# LoRa.net
KiCad netlist of a schematic drawn in Altium Designer
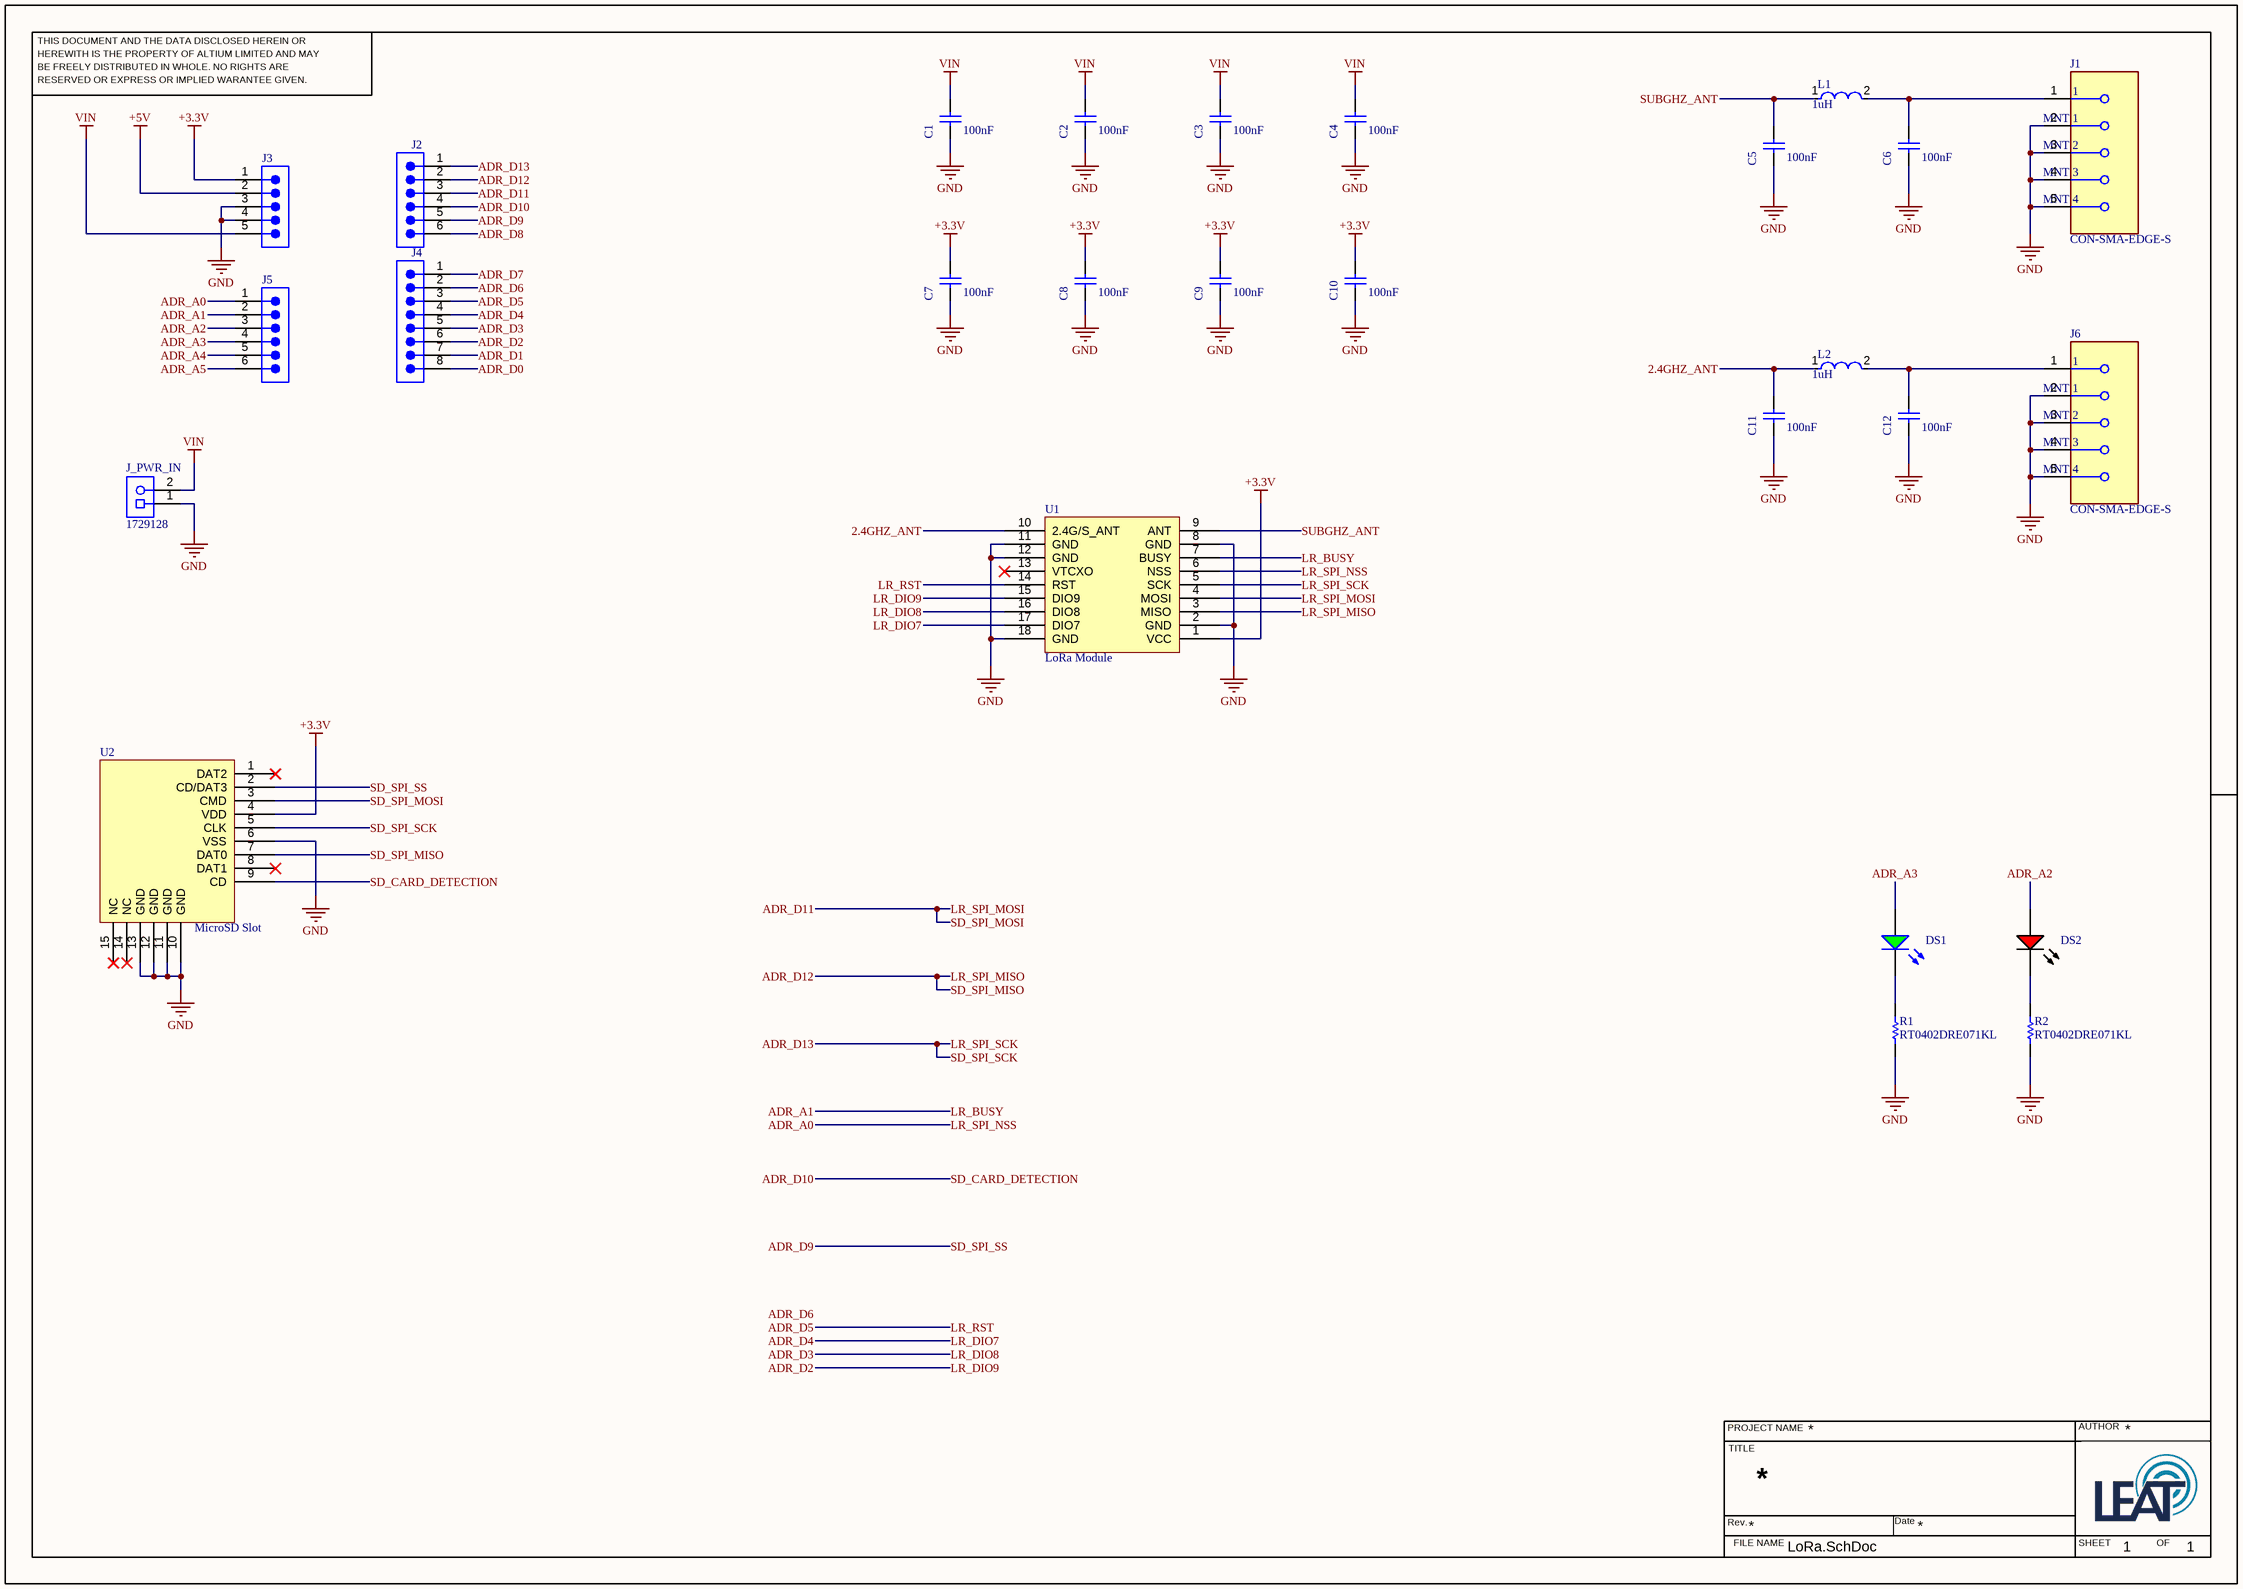
[diagram p0: LoRa.SchDoc]

(export (version "E")
  (design (tool "Eeschema 10.0.6"))
  (components
    (comp (ref "C1")
      (value "885012205037")
      (footprint "WCAP-CSGP_0402_L1W0.5H0.5")
      (description "Cap Ceramic 0.1uF 16V X7R 10% Pad SMD 0402 125C T/R")
      (fields (field (name "CAPACITANCE") "100nF") (field (name "TOLERANCE") "10%"))
      (libsource (lib "Altium Content Vault") (part "Capacitor_Non-Polarized"))
    )
    (comp (ref "C2")
      (value "885012205037")
      (footprint "WCAP-CSGP_0402_L1W0.5H0.5")
      (description "Cap Ceramic 0.1uF 16V X7R 10% Pad SMD 0402 125C T/R")
      (fields (field (name "CAPACITANCE") "100nF") (field (name "TOLERANCE") "10%"))
      (libsource (lib "Altium Content Vault") (part "Capacitor_Non-Polarized"))
    )
    (comp (ref "C3")
      (value "885012205037")
      (footprint "WCAP-CSGP_0402_L1W0.5H0.5")
      (description "Cap Ceramic 0.1uF 16V X7R 10% Pad SMD 0402 125C T/R")
      (fields (field (name "CAPACITANCE") "100nF") (field (name "TOLERANCE") "10%"))
      (libsource (lib "Altium Content Vault") (part "Capacitor_Non-Polarized"))
    )
    (comp (ref "C4")
      (value "885012205037")
      (footprint "WCAP-CSGP_0402_L1W0.5H0.5")
      (description "Cap Ceramic 0.1uF 16V X7R 10% Pad SMD 0402 125C T/R")
      (fields (field (name "CAPACITANCE") "100nF") (field (name "TOLERANCE") "10%"))
      (libsource (lib "Altium Content Vault") (part "Capacitor_Non-Polarized"))
    )
    (comp (ref "C5")
      (value "885012205037")
      (footprint "WCAP-CSGP_0402_L1W0.5H0.5")
      (description "Cap Ceramic 0.1uF 16V X7R 10% Pad SMD 0402 125C T/R")
      (fields (field (name "CAPACITANCE") "100nF") (field (name "TOLERANCE") "10%"))
      (libsource (lib "Altium Content Vault") (part "Capacitor_Non-Polarized"))
    )
    (comp (ref "C6")
      (value "885012205037")
      (footprint "WCAP-CSGP_0402_L1W0.5H0.5")
      (description "Cap Ceramic 0.1uF 16V X7R 10% Pad SMD 0402 125C T/R")
      (fields (field (name "CAPACITANCE") "100nF") (field (name "TOLERANCE") "10%"))
      (libsource (lib "Altium Content Vault") (part "Capacitor_Non-Polarized"))
    )
    (comp (ref "C7")
      (value "885012205037")
      (footprint "WCAP-CSGP_0402_L1W0.5H0.5")
      (description "Cap Ceramic 0.1uF 16V X7R 10% Pad SMD 0402 125C T/R")
      (fields (field (name "CAPACITANCE") "100nF") (field (name "TOLERANCE") "10%"))
      (libsource (lib "Altium Content Vault") (part "Capacitor_Non-Polarized"))
    )
    (comp (ref "C8")
      (value "885012205037")
      (footprint "WCAP-CSGP_0402_L1W0.5H0.5")
      (description "Cap Ceramic 0.1uF 16V X7R 10% Pad SMD 0402 125C T/R")
      (fields (field (name "CAPACITANCE") "100nF") (field (name "TOLERANCE") "10%"))
      (libsource (lib "Altium Content Vault") (part "Capacitor_Non-Polarized"))
    )
    (comp (ref "C9")
      (value "885012205037")
      (footprint "WCAP-CSGP_0402_L1W0.5H0.5")
      (description "Cap Ceramic 0.1uF 16V X7R 10% Pad SMD 0402 125C T/R")
      (fields (field (name "CAPACITANCE") "100nF") (field (name "TOLERANCE") "10%"))
      (libsource (lib "Altium Content Vault") (part "Capacitor_Non-Polarized"))
    )
    (comp (ref "C10")
      (value "885012205037")
      (footprint "WCAP-CSGP_0402_L1W0.5H0.5")
      (description "Cap Ceramic 0.1uF 16V X7R 10% Pad SMD 0402 125C T/R")
      (fields (field (name "CAPACITANCE") "100nF") (field (name "TOLERANCE") "10%"))
      (libsource (lib "Altium Content Vault") (part "Capacitor_Non-Polarized"))
    )
    (comp (ref "C11")
      (value "885012205037")
      (footprint "WCAP-CSGP_0402_L1W0.5H0.5")
      (description "Cap Ceramic 0.1uF 16V X7R 10% Pad SMD 0402 125C T/R")
      (fields (field (name "CAPACITANCE") "100nF") (field (name "TOLERANCE") "10%"))
      (libsource (lib "Altium Content Vault") (part "Capacitor_Non-Polarized"))
    )
    (comp (ref "C12")
      (value "885012205037")
      (footprint "WCAP-CSGP_0402_L1W0.5H0.5")
      (description "Cap Ceramic 0.1uF 16V X7R 10% Pad SMD 0402 125C T/R")
      (fields (field (name "CAPACITANCE") "100nF") (field (name "TOLERANCE") "10%"))
      (libsource (lib "Altium Content Vault") (part "Capacitor_Non-Polarized"))
    )
    (comp (ref "DS1")
      (value "LTST-S220GKT")
      (footprint "LTST-S220GKT_V")
      (description "LED Green, 100 mW, 30 mA, -55 to 85 degC, 2-Pin SMD, RoHS, Tape and Reel")
      (fields (field (name "MANUFACTURER") "Lite-On"))
      (libsource (lib "Altium Content Vault") (part "LED-GREEN-AK-2"))
    )
    (comp (ref "DS2")
      (value "LTST-C170KRKT")
      (footprint "LTST-C170KRKT_V")
      (description "LED Red, 75 mW, 54 mcd, -55 to 85 degC, 2-Pin SMD, RoHS, Tape and Reel")
      (fields (field (name "MANUFACTURER") "Lite-On"))
      (libsource (lib "Altium Content Vault") (part "LED-RED-AK-2"))
    )
    (comp (ref "J1")
      (value "CON-SMA-EDGE-S")
      (footprint "FP-CON-SMA-EDGE-S-MFG")
      (description "CONN SMA JACK STR EDGE MNT")
      (fields
        (field (name "OCTOPART") "https://octopart.com/con-sma-edge-s-rf+solutions-70967450")
        (field (name "MANUFACTURER") "RF Solutions Ltd.")
      )
      (libsource (lib "Altium Content Vault") (part "a163d97a771fcdd2fd1f1a9264c171f"))
    )
    (comp (ref "J2")
      (value "61300611121")
      (footprint "61300611121")
      (description "THT Vertical Pin Header WR-PHD, Pitch 2.54 mm, Single Row, 6 pins")
      (libsource (lib "Altium Content Vault") (part "Header_Male_1R_06P"))
    )
    (comp (ref "J3")
      (value "61300511121")
      (footprint "61300511121")
      (description "THT Vertical Pin Header WR-PHD, Pitch 2.54 mm, Single Row, 5 pins")
      (libsource (lib "Altium Content Vault") (part "Header_Male_1R_05P"))
    )
    (comp (ref "J4")
      (value "61300811121")
      (footprint "61300811121")
      (description "THT Vertical Pin Header WR-PHD, Pitch 2.54 mm, Single Row, 8 pins")
      (libsource (lib "Altium Content Vault") (part "Header_Male_1R_08P"))
    )
    (comp (ref "J5")
      (value "61300611121")
      (footprint "61300611121")
      (description "THT Vertical Pin Header WR-PHD, Pitch 2.54 mm, Single Row, 6 pins")
      (libsource (lib "Altium Content Vault") (part "Header_Male_1R_06P"))
    )
    (comp (ref "J6")
      (value "CON-SMA-EDGE-S")
      (footprint "FP-CON-SMA-EDGE-S-MFG")
      (description "CONN SMA JACK STR EDGE MNT")
      (fields
        (field (name "OCTOPART") "https://octopart.com/con-sma-edge-s-rf+solutions-70967450")
        (field (name "MANUFACTURER") "RF Solutions Ltd.")
      )
      (libsource (lib "Altium Content Vault") (part "a163d97a771fcdd2fd1f1a9264c171f"))
    )
    (comp (ref "J_PWR_IN")
      (value "1729128")
      (footprint "PHOE-1729128-2_V")
      (description "PCB Terminal Block, 13.5 A, 400 V, 2-Pin THD, RoHS, Bulk")
      (fields (field (name "MANUFACTURER") "Phoenix Contact"))
      (libsource (lib "Altium Content Vault") (part "CN-2P-F-R2"))
    )
    (comp (ref "L1")
      (value "MLZ1005M1R0WT000")
      (footprint "FP-MLZ1005-MFG")
      (description "Shielded Multilayer Inductor 1uH ±20% 450mA 455mΩ SMD 0402")
      (fields (field (name "TOLERANCE") "20%") (field (name "INDUCTANCE") "1uH"))
      (libsource (lib "Altium Content Vault") (part "725321dda6339637d4d059423bc1c3c"))
    )
    (comp (ref "L2")
      (value "MLZ1005M1R0WT000")
      (footprint "FP-MLZ1005-MFG")
      (description "Shielded Multilayer Inductor 1uH ±20% 450mA 455mΩ SMD 0402")
      (fields (field (name "TOLERANCE") "20%") (field (name "INDUCTANCE") "1uH"))
      (libsource (lib "Altium Content Vault") (part "725321dda6339637d4d059423bc1c3c"))
    )
    (comp (ref "R1")
      (value "RT0402DRE071KL")
      (footprint "RESC1005X35X25ML10T10")
      (fields (field (name "MANUFACTURER") "Yageo"))
      (libsource (lib "Altium Content Vault") (part "RES"))
    )
    (comp (ref "R2")
      (value "RT0402DRE071KL")
      (footprint "RESC1005X35X25ML10T10")
      (fields (field (name "MANUFACTURER") "Yageo"))
      (libsource (lib "Altium Content Vault") (part "RES"))
    )
    (comp (ref "U1")
      (value "LoRa Module")
      (footprint "LR2021")
      (description "LoRa2021: 160mW Multi-Band Wireless Communication Module")
      (libsource (lib "NiceRF_LR2021") (part "LR2021"))
    )
    (comp (ref "U2")
      (value "MicroSD Slot")
      (footprint "TF-01A")
      (description "1.85mm Card Slot MicroSD card (TF card) Self-bouncing SMD SD Card / Memory Card Connector ROHS")
      (libsource (lib "TF-01A") (part "TF-01A"))
    )
  )
  (nets
    (net (code "1") (name "+3.3V") (class "Default")
      (node (ref "C10") (pin "2") (pinfunction "2_2") (pintype "passive"))
      (node (ref "C7") (pin "2") (pinfunction "2_2") (pintype "passive"))
      (node (ref "C8") (pin "2") (pinfunction "2_2") (pintype "passive"))
      (node (ref "C9") (pin "2") (pinfunction "2_2") (pintype "passive"))
      (node (ref "J3") (pin "1") (pinfunction "1_1") (pintype "passive"))
      (node (ref "U1") (pin "1") (pinfunction "VCC_1") (pintype "passive"))
      (node (ref "U2") (pin "4") (pinfunction "VDD_4") (pintype "passive"))
    )
    (net (code "2") (name "+5V") (class "Default")
      (node (ref "J3") (pin "2") (pinfunction "2_2") (pintype "passive"))
    )
    (net (code "3") (name "/2.4GHZ_ANT") (class "Default")
      (node (ref "C11") (pin "2") (pinfunction "2_2") (pintype "passive"))
      (node (ref "L2") (pin "1") (pinfunction "1_1") (pintype "passive"))
      (node (ref "U1") (pin "10") (pinfunction "2.4G/S_ANT_10") (pintype "passive"))
    )
    (net (code "4") (name "/ADR_A0") (class "Default")
      (node (ref "J5") (pin "1") (pinfunction "1_1") (pintype "passive"))
      (node (ref "U1") (pin "6") (pinfunction "NSS_6") (pintype "passive"))
    )
    (net (code "5") (name "/ADR_A1") (class "Default")
      (node (ref "J5") (pin "2") (pinfunction "2_2") (pintype "passive"))
      (node (ref "U1") (pin "7") (pinfunction "BUSY_7") (pintype "passive"))
    )
    (net (code "6") (name "/ADR_A2") (class "Default")
      (node (ref "DS2") (pin "1") (pinfunction "A_1") (pintype "passive"))
      (node (ref "J5") (pin "3") (pinfunction "3_3") (pintype "passive"))
    )
    (net (code "7") (name "/ADR_A3") (class "Default")
      (node (ref "DS1") (pin "1") (pinfunction "A_1") (pintype "passive"))
      (node (ref "J5") (pin "4") (pinfunction "4_4") (pintype "passive"))
    )
    (net (code "8") (name "/ADR_A4") (class "Default")
      (node (ref "J5") (pin "5") (pinfunction "5_5") (pintype "passive"))
    )
    (net (code "9") (name "/ADR_A5") (class "Default")
      (node (ref "J5") (pin "6") (pinfunction "6_6") (pintype "passive"))
    )
    (net (code "10") (name "/ADR_D0") (class "Default")
      (node (ref "J4") (pin "8") (pinfunction "8_8") (pintype "passive"))
    )
    (net (code "11") (name "/ADR_D1") (class "Default")
      (node (ref "J4") (pin "7") (pinfunction "7_7") (pintype "passive"))
    )
    (net (code "12") (name "/ADR_D2") (class "Default")
      (node (ref "J4") (pin "6") (pinfunction "6_6") (pintype "passive"))
      (node (ref "U1") (pin "15") (pinfunction "DIO9_15") (pintype "passive"))
    )
    (net (code "13") (name "/ADR_D3") (class "Default")
      (node (ref "J4") (pin "5") (pinfunction "5_5") (pintype "passive"))
      (node (ref "U1") (pin "16") (pinfunction "DIO8_16") (pintype "passive"))
    )
    (net (code "14") (name "/ADR_D4") (class "Default")
      (node (ref "J4") (pin "4") (pinfunction "4_4") (pintype "passive"))
      (node (ref "U1") (pin "17") (pinfunction "DIO7_17") (pintype "passive"))
    )
    (net (code "15") (name "/ADR_D5") (class "Default")
      (node (ref "J4") (pin "3") (pinfunction "3_3") (pintype "passive"))
      (node (ref "U1") (pin "14") (pinfunction "RST_14") (pintype "passive"))
    )
    (net (code "16") (name "/ADR_D6") (class "Default")
      (node (ref "J4") (pin "2") (pinfunction "2_2") (pintype "passive"))
    )
    (net (code "17") (name "/ADR_D7") (class "Default")
      (node (ref "J4") (pin "1") (pinfunction "1_1") (pintype "passive"))
    )
    (net (code "18") (name "/ADR_D8") (class "Default")
      (node (ref "J2") (pin "6") (pinfunction "6_6") (pintype "passive"))
    )
    (net (code "19") (name "/ADR_D9") (class "Default")
      (node (ref "J2") (pin "5") (pinfunction "5_5") (pintype "passive"))
      (node (ref "U2") (pin "2") (pinfunction "CD/DAT3_2") (pintype "passive"))
    )
    (net (code "20") (name "/ADR_D10") (class "Default")
      (node (ref "J2") (pin "4") (pinfunction "4_4") (pintype "passive"))
      (node (ref "U2") (pin "9") (pinfunction "CD_9") (pintype "passive"))
    )
    (net (code "21") (name "/ADR_D11") (class "Default")
      (node (ref "J2") (pin "3") (pinfunction "3_3") (pintype "passive"))
      (node (ref "U1") (pin "4") (pinfunction "MOSI_4") (pintype "passive"))
      (node (ref "U2") (pin "3") (pinfunction "CMD_3") (pintype "passive"))
    )
    (net (code "22") (name "/ADR_D12") (class "Default")
      (node (ref "J2") (pin "2") (pinfunction "2_2") (pintype "passive"))
      (node (ref "U1") (pin "3") (pinfunction "MISO_3") (pintype "passive"))
      (node (ref "U2") (pin "7") (pinfunction "DAT0_7") (pintype "passive"))
    )
    (net (code "23") (name "/ADR_D13") (class "Default")
      (node (ref "J2") (pin "1") (pinfunction "1_1") (pintype "passive"))
      (node (ref "U1") (pin "5") (pinfunction "SCK_5") (pintype "passive"))
      (node (ref "U2") (pin "5") (pinfunction "CLK_5") (pintype "passive"))
    )
    (net (code "24") (name "/SUBGHZ_ANT") (class "Default")
      (node (ref "C5") (pin "2") (pinfunction "2_2") (pintype "passive"))
      (node (ref "L1") (pin "1") (pinfunction "1_1") (pintype "passive"))
      (node (ref "U1") (pin "9") (pinfunction "ANT_9") (pintype "passive"))
    )
    (net (code "25") (name "GND") (class "Default")
      (node (ref "C1") (pin "1") (pinfunction "1_1") (pintype "passive"))
      (node (ref "C10") (pin "1") (pinfunction "1_1") (pintype "passive"))
      (node (ref "C11") (pin "1") (pinfunction "1_1") (pintype "passive"))
      (node (ref "C12") (pin "1") (pinfunction "1_1") (pintype "passive"))
      (node (ref "C2") (pin "1") (pinfunction "1_1") (pintype "passive"))
      (node (ref "C3") (pin "1") (pinfunction "1_1") (pintype "passive"))
      (node (ref "C4") (pin "1") (pinfunction "1_1") (pintype "passive"))
      (node (ref "C5") (pin "1") (pinfunction "1_1") (pintype "passive"))
      (node (ref "C6") (pin "1") (pinfunction "1_1") (pintype "passive"))
      (node (ref "C7") (pin "1") (pinfunction "1_1") (pintype "passive"))
      (node (ref "C8") (pin "1") (pinfunction "1_1") (pintype "passive"))
      (node (ref "C9") (pin "1") (pinfunction "1_1") (pintype "passive"))
      (node (ref "J1") (pin "2") (pinfunction "MNT_1_2") (pintype "passive"))
      (node (ref "J1") (pin "3") (pinfunction "MNT_2_3") (pintype "passive"))
      (node (ref "J1") (pin "4") (pinfunction "MNT_3_4") (pintype "passive"))
      (node (ref "J1") (pin "5") (pinfunction "MNT_4_5") (pintype "passive"))
      (node (ref "J3") (pin "3") (pinfunction "3_3") (pintype "passive"))
      (node (ref "J3") (pin "4") (pinfunction "4_4") (pintype "passive"))
      (node (ref "J6") (pin "2") (pinfunction "MNT_1_2") (pintype "passive"))
      (node (ref "J6") (pin "3") (pinfunction "MNT_2_3") (pintype "passive"))
      (node (ref "J6") (pin "4") (pinfunction "MNT_3_4") (pintype "passive"))
      (node (ref "J6") (pin "5") (pinfunction "MNT_4_5") (pintype "passive"))
      (node (ref "J_PWR_IN") (pin "1") (pinfunction "1_1") (pintype "passive"))
      (node (ref "R1") (pin "1") (pinfunction "1_1") (pintype "passive"))
      (node (ref "R2") (pin "1") (pinfunction "1_1") (pintype "passive"))
      (node (ref "U1") (pin "11") (pinfunction "GND_11") (pintype "passive"))
      (node (ref "U1") (pin "12") (pinfunction "GND_12") (pintype "passive"))
      (node (ref "U1") (pin "18") (pinfunction "GND_18") (pintype "passive"))
      (node (ref "U1") (pin "2") (pinfunction "GND_2") (pintype "passive"))
      (node (ref "U1") (pin "8") (pinfunction "GND_8") (pintype "passive"))
      (node (ref "U2") (pin "10") (pinfunction "GND_10") (pintype "passive"))
      (node (ref "U2") (pin "11") (pinfunction "GND_11") (pintype "passive"))
      (node (ref "U2") (pin "12") (pinfunction "GND_12") (pintype "passive"))
      (node (ref "U2") (pin "13") (pinfunction "GND_13") (pintype "passive"))
      (node (ref "U2") (pin "6") (pinfunction "VSS_6") (pintype "passive"))
    )
    (net (code "26") (name "Net-(C6-Pad2)") (class "Default")
      (node (ref "C6") (pin "2") (pinfunction "2_2") (pintype "passive"))
      (node (ref "J1") (pin "1") (pinfunction "1_1") (pintype "passive"))
      (node (ref "L1") (pin "2") (pinfunction "2_2") (pintype "passive"))
    )
    (net (code "27") (name "Net-(C12-Pad2)") (class "Default")
      (node (ref "C12") (pin "2") (pinfunction "2_2") (pintype "passive"))
      (node (ref "J6") (pin "1") (pinfunction "1_1") (pintype "passive"))
      (node (ref "L2") (pin "2") (pinfunction "2_2") (pintype "passive"))
    )
    (net (code "28") (name "Net-(DS1-K)") (class "Default")
      (node (ref "DS1") (pin "2") (pinfunction "K_2") (pintype "passive"))
      (node (ref "R1") (pin "2") (pinfunction "2_2") (pintype "passive"))
    )
    (net (code "29") (name "Net-(DS2-K)") (class "Default")
      (node (ref "DS2") (pin "2") (pinfunction "K_2") (pintype "passive"))
      (node (ref "R2") (pin "2") (pinfunction "2_2") (pintype "passive"))
    )
    (net (code "30") (name "VIN") (class "Default")
      (node (ref "C1") (pin "2") (pinfunction "2_2") (pintype "passive"))
      (node (ref "C2") (pin "2") (pinfunction "2_2") (pintype "passive"))
      (node (ref "C3") (pin "2") (pinfunction "2_2") (pintype "passive"))
      (node (ref "C4") (pin "2") (pinfunction "2_2") (pintype "passive"))
      (node (ref "J3") (pin "5") (pinfunction "5_5") (pintype "passive"))
      (node (ref "J_PWR_IN") (pin "2") (pinfunction "2_2") (pintype "passive"))
    )
    (net (code "31") (name "unconnected-(U1-VTCXO-Pad13)") (class "Default")
      (node (ref "U1") (pin "13") (pinfunction "VTCXO_13") (pintype "passive+no_connect"))
    )
    (net (code "32") (name "unconnected-(U2-DAT1-Pad8)") (class "Default")
      (node (ref "U2") (pin "8") (pinfunction "DAT1_8") (pintype "passive+no_connect"))
    )
    (net (code "33") (name "unconnected-(U2-DAT2-Pad1)") (class "Default")
      (node (ref "U2") (pin "1") (pinfunction "DAT2_1") (pintype "passive+no_connect"))
    )
    (net (code "34") (name "unconnected-(U2-NC-Pad14)") (class "Default")
      (node (ref "U2") (pin "14") (pinfunction "NC_14") (pintype "passive+no_connect"))
    )
    (net (code "35") (name "unconnected-(U2-NC-Pad15)") (class "Default")
      (node (ref "U2") (pin "15") (pinfunction "NC_15") (pintype "passive+no_connect"))
    )
  )
)
